# rgbstripe_fft_lochraster.net
KiCad netlist of a schematic drawn in EAGLE
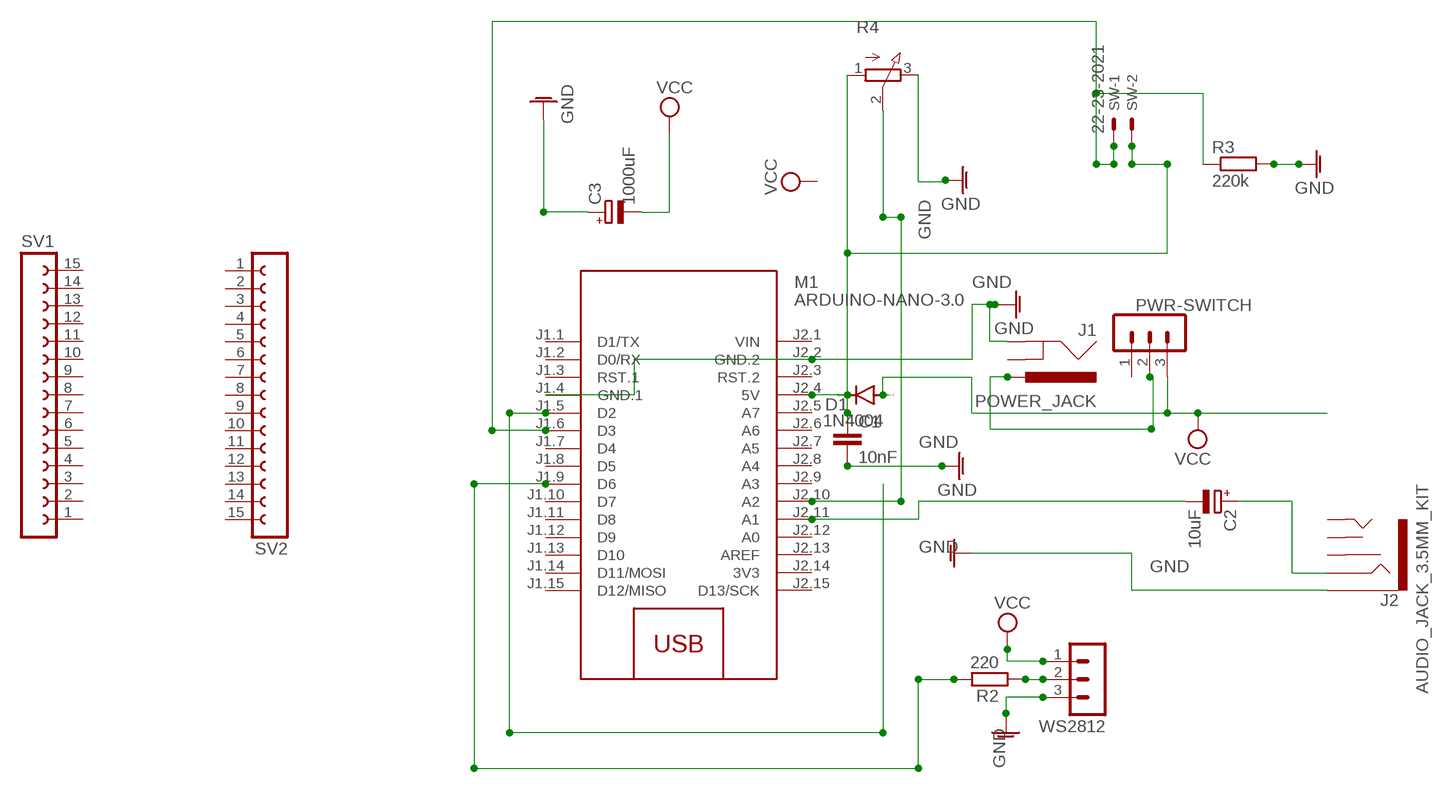
[diagram p0: schematic, sheet 1]

(export (version "E")
  (design (tool "Eeschema 10.0.6"))
  (components
    (comp (ref "C1")
      (value "10nF")
      (footprint "eagle-import:C050-024X044")
      (libsource (lib "eagle-import") (part "C-EU050-024X044"))
    )
    (comp (ref "C2")
      (value "10uF")
      (footprint "eagle-import:E2,5-6")
      (libsource (lib "eagle-import") (part "CPOL-EUE2.5-6"))
    )
    (comp (ref "C3")
      (value "1000uF")
      (footprint "eagle-import:E3,5-8")
      (libsource (lib "eagle-import") (part "CPOL-EUE3.5-8"))
    )
    (comp (ref "D1")
      (value "1N4004")
      (footprint "eagle-import:DO41-10")
      (libsource (lib "eagle-import") (part "1N4004"))
    )
    (comp (ref "J1")
      (value "POWER_JACK")
      (footprint "eagle-import:POWER_JACK_PTH")
      (libsource (lib "eagle-import") (part "POWER_JACK"))
    )
    (comp (ref "J2")
      (value "AUDIO_JACK_3.5MM_KIT")
      (footprint "eagle-import:AUDIO-JACK-KIT")
      (libsource (lib "eagle-import") (part "AUDIO_JACK_3.5MM_KIT"))
    )
    (comp (ref "M1")
      (value "ARDUINO-NANO-3.0")
      (footprint "eagle-import:ARDUINO-NANO-3.0")
      (libsource (lib "eagle-import") (part "ARDUINO-NANO-3.0"))
    )
    (comp (ref "PWR-SWITCH")
      (value "MA03-1")
      (footprint "eagle-import:MA03-1")
      (libsource (lib "eagle-import") (part "MA03-1"))
    )
    (comp (ref "R2")
      (value "220")
      (footprint "eagle-import:0204_5")
      (libsource (lib "eagle-import") (part "R-EU_0204/5"))
    )
    (comp (ref "R3")
      (value "220k")
      (footprint "eagle-import:0204_7")
      (libsource (lib "eagle-import") (part "R-EU_0204/7"))
    )
    (comp (ref "R4")
      (value "3RP/1610N")
      (footprint "eagle-import:3RP_1610N")
      (libsource (lib "eagle-import") (part "3RP/1610N"))
    )
    (comp (ref "SV1")
      (value "FE15-1")
      (footprint "eagle-import:FE15")
      (libsource (lib "eagle-import") (part "FE15-1"))
    )
    (comp (ref "SV2")
      (value "FE15-1")
      (footprint "eagle-import:FE15")
      (libsource (lib "eagle-import") (part "FE15-1"))
    )
    (comp (ref "SW")
      (value "22-23-2021")
      (footprint "eagle-import:22-23-2021")
      (fields (field (name "MF") "MOLEX"))
      (libsource (lib "eagle-import") (part "22-23-2021"))
    )
    (comp (ref "WS2812")
      (value "MA03-1")
      (footprint "eagle-import:MA03-1")
      (libsource (lib "eagle-import") (part "MA03-1"))
    )
  )
  (nets
    (net (code "1") (name "/3V3") (class "Default")
      (node (ref "M1") (pin "J2.14") (pinfunction "3V3_J2.14") (pintype "power_in"))
    )
    (net (code "2") (name "/VIN") (class "Default")
      (node (ref "M1") (pin "J2.1") (pinfunction "VIN_J2.1") (pintype "power_in"))
    )
    (net (code "3") (name "GND") (class "Default")
      (node (ref "C1") (pin "2") (pinfunction "2_2") (pintype "passive"))
      (node (ref "C3") (pin "+") (pinfunction "+_+") (pintype "passive"))
      (node (ref "J1") (pin "GND") (pinfunction "GND_GND") (pintype "bidirectional"))
      (node (ref "J2") (pin "SLEEVE") (pinfunction "SLEEVE_SLEEVE") (pintype "bidirectional"))
      (node (ref "M1") (pin "J1.4") (pinfunction "GND.1_J1.4") (pintype "power_in"))
      (node (ref "M1") (pin "J2.2") (pinfunction "GND.2_J2.2") (pintype "power_in"))
      (node (ref "R3") (pin "2") (pinfunction "2_2") (pintype "passive"))
      (node (ref "R4") (pin "3") (pinfunction "E_3") (pintype "passive"))
      (node (ref "WS2812") (pin "3") (pinfunction "3_3") (pintype "passive"))
    )
    (net (code "4") (name "Net-(C2-Pad+)") (class "Default")
      (node (ref "C2") (pin "+") (pinfunction "+_+") (pintype "passive"))
      (node (ref "J2") (pin "RING") (pinfunction "RING_RING") (pintype "bidirectional"))
    )
    (net (code "5") (name "Net-(J1-PadPWR)") (class "Default")
      (node (ref "J1") (pin "PWR") (pinfunction "PWR_PWR") (pintype "bidirectional"))
      (node (ref "PWR-SWITCH") (pin "2") (pinfunction "2_2") (pintype "passive"))
    )
    (net (code "6") (name "Net-(M1-5V)") (class "Default")
      (node (ref "C1") (pin "1") (pinfunction "1_1") (pintype "passive"))
      (node (ref "D1") (pin "C") (pinfunction "C_C") (pintype "passive"))
      (node (ref "M1") (pin "J2.4") (pinfunction "5V_J2.4") (pintype "power_in"))
      (node (ref "R4") (pin "1") (pinfunction "A_1") (pintype "passive"))
      (node (ref "SW") (pin "2") (pinfunction "S_2") (pintype "passive"))
    )
    (net (code "7") (name "Net-(M1-A1)") (class "Default")
      (node (ref "C2") (pin "-") (pinfunction "-_-") (pintype "passive"))
      (node (ref "M1") (pin "J2.11") (pinfunction "A1_J2.11") (pintype "bidirectional"))
    )
    (net (code "8") (name "Net-(M1-A2)") (class "Default")
      (node (ref "M1") (pin "J2.10") (pinfunction "A2_J2.10") (pintype "bidirectional"))
      (node (ref "R4") (pin "2") (pinfunction "S_2") (pintype "passive"))
    )
    (net (code "9") (name "Net-(M1-D3)") (class "Default")
      (node (ref "M1") (pin "J1.6") (pinfunction "D3_J1.6") (pintype "bidirectional"))
      (node (ref "R3") (pin "1") (pinfunction "1_1") (pintype "passive"))
      (node (ref "SW") (pin "1") (pinfunction "S_1") (pintype "passive"))
    )
    (net (code "10") (name "Net-(M1-D6)") (class "Default")
      (node (ref "M1") (pin "J1.9") (pinfunction "D6_J1.9") (pintype "bidirectional"))
      (node (ref "R2") (pin "2") (pinfunction "2_2") (pintype "passive"))
    )
    (net (code "11") (name "Net-(R2-Pad1)") (class "Default")
      (node (ref "R2") (pin "1") (pinfunction "1_1") (pintype "passive"))
      (node (ref "WS2812") (pin "2") (pinfunction "2_2") (pintype "passive"))
    )
    (net (code "12") (name "VCC") (class "Default")
      (node (ref "C3") (pin "-") (pinfunction "-_-") (pintype "passive"))
      (node (ref "D1") (pin "A") (pinfunction "A_A") (pintype "passive"))
      (node (ref "PWR-SWITCH") (pin "3") (pinfunction "3_3") (pintype "passive"))
      (node (ref "WS2812") (pin "1") (pinfunction "1_1") (pintype "passive"))
    )
    (net (code "13") (name "unconnected-(J1-PadGNDBREAK)") (class "Default")
      (node (ref "J1") (pin "GNDBREAK") (pinfunction "GNDBREAK_GNDBREAK") (pintype "bidirectional"))
    )
    (net (code "14") (name "unconnected-(J2-PadRSH)") (class "Default")
      (node (ref "J2") (pin "RSH") (pinfunction "RSH_RSH") (pintype "bidirectional"))
    )
    (net (code "15") (name "unconnected-(J2-PadTIP)") (class "Default")
      (node (ref "J2") (pin "TIP") (pinfunction "TIP_TIP") (pintype "bidirectional"))
    )
    (net (code "16") (name "unconnected-(J2-PadTSH)") (class "Default")
      (node (ref "J2") (pin "TSH") (pinfunction "TSH_TSH") (pintype "bidirectional"))
    )
    (net (code "17") (name "unconnected-(M1-A0-PadJ2.12)") (class "Default")
      (node (ref "M1") (pin "J2.12") (pinfunction "A0_J2.12") (pintype "bidirectional"))
    )
    (net (code "18") (name "unconnected-(M1-A3-PadJ2.9)") (class "Default")
      (node (ref "M1") (pin "J2.9") (pinfunction "A3_J2.9") (pintype "bidirectional"))
    )
    (net (code "19") (name "unconnected-(M1-A4-PadJ2.8)") (class "Default")
      (node (ref "M1") (pin "J2.8") (pinfunction "A4_J2.8") (pintype "bidirectional"))
    )
    (net (code "20") (name "unconnected-(M1-A5-PadJ2.7)") (class "Default")
      (node (ref "M1") (pin "J2.7") (pinfunction "A5_J2.7") (pintype "bidirectional"))
    )
    (net (code "21") (name "unconnected-(M1-A6-PadJ2.6)") (class "Default")
      (node (ref "M1") (pin "J2.6") (pinfunction "A6_J2.6") (pintype "bidirectional"))
    )
    (net (code "22") (name "unconnected-(M1-A7-PadJ2.5)") (class "Default")
      (node (ref "M1") (pin "J2.5") (pinfunction "A7_J2.5") (pintype "bidirectional"))
    )
    (net (code "23") (name "unconnected-(M1-AREF-PadJ2.13)") (class "Default")
      (node (ref "M1") (pin "J2.13") (pinfunction "AREF_J2.13") (pintype "bidirectional"))
    )
    (net (code "24") (name "unconnected-(M1-D0{slash}RX-PadJ1.2)") (class "Default")
      (node (ref "M1") (pin "J1.2") (pinfunction "D0/RX_J1.2") (pintype "bidirectional"))
    )
    (net (code "25") (name "unconnected-(M1-D1{slash}TX-PadJ1.1)") (class "Default")
      (node (ref "M1") (pin "J1.1") (pinfunction "D1/TX_J1.1") (pintype "bidirectional"))
    )
    (net (code "26") (name "unconnected-(M1-D2-PadJ1.5)") (class "Default")
      (node (ref "M1") (pin "J1.5") (pinfunction "D2_J1.5") (pintype "bidirectional"))
    )
    (net (code "27") (name "unconnected-(M1-D4-PadJ1.7)") (class "Default")
      (node (ref "M1") (pin "J1.7") (pinfunction "D4_J1.7") (pintype "bidirectional"))
    )
    (net (code "28") (name "unconnected-(M1-D5-PadJ1.8)") (class "Default")
      (node (ref "M1") (pin "J1.8") (pinfunction "D5_J1.8") (pintype "bidirectional"))
    )
    (net (code "29") (name "unconnected-(M1-D7-PadJ1.10)") (class "Default")
      (node (ref "M1") (pin "J1.10") (pinfunction "D7_J1.10") (pintype "bidirectional"))
    )
    (net (code "30") (name "unconnected-(M1-D8-PadJ1.11)") (class "Default")
      (node (ref "M1") (pin "J1.11") (pinfunction "D8_J1.11") (pintype "bidirectional"))
    )
    (net (code "31") (name "unconnected-(M1-D9-PadJ1.12)") (class "Default")
      (node (ref "M1") (pin "J1.12") (pinfunction "D9_J1.12") (pintype "bidirectional"))
    )
    (net (code "32") (name "unconnected-(M1-D10-PadJ1.13)") (class "Default")
      (node (ref "M1") (pin "J1.13") (pinfunction "D10_J1.13") (pintype "bidirectional"))
    )
    (net (code "33") (name "unconnected-(M1-D11{slash}MOSI-PadJ1.14)") (class "Default")
      (node (ref "M1") (pin "J1.14") (pinfunction "D11/MOSI_J1.14") (pintype "bidirectional"))
    )
    (net (code "34") (name "unconnected-(M1-D12{slash}MISO-PadJ1.15)") (class "Default")
      (node (ref "M1") (pin "J1.15") (pinfunction "D12/MISO_J1.15") (pintype "bidirectional"))
    )
    (net (code "35") (name "unconnected-(M1-D13{slash}SCK-PadJ2.15)") (class "Default")
      (node (ref "M1") (pin "J2.15") (pinfunction "D13/SCK_J2.15") (pintype "bidirectional"))
    )
    (net (code "36") (name "unconnected-(M1-RST.1-PadJ1.3)") (class "Default")
      (node (ref "M1") (pin "J1.3") (pinfunction "RST.1_J1.3") (pintype "bidirectional"))
    )
    (net (code "37") (name "unconnected-(M1-RST.2-PadJ2.3)") (class "Default")
      (node (ref "M1") (pin "J2.3") (pinfunction "RST.2_J2.3") (pintype "bidirectional"))
    )
    (net (code "38") (name "unconnected-(PWR-SWITCH-Pad1)") (class "Default")
      (node (ref "PWR-SWITCH") (pin "1") (pinfunction "1_1") (pintype "passive"))
    )
    (net (code "39") (name "unconnected-(SV1-Pad1)") (class "Default")
      (node (ref "SV1") (pin "1") (pinfunction "1_1") (pintype "passive"))
    )
    (net (code "40") (name "unconnected-(SV1-Pad2)") (class "Default")
      (node (ref "SV1") (pin "2") (pinfunction "2_2") (pintype "passive"))
    )
    (net (code "41") (name "unconnected-(SV1-Pad3)") (class "Default")
      (node (ref "SV1") (pin "3") (pinfunction "3_3") (pintype "passive"))
    )
    (net (code "42") (name "unconnected-(SV1-Pad4)") (class "Default")
      (node (ref "SV1") (pin "4") (pinfunction "4_4") (pintype "passive"))
    )
    (net (code "43") (name "unconnected-(SV1-Pad5)") (class "Default")
      (node (ref "SV1") (pin "5") (pinfunction "5_5") (pintype "passive"))
    )
    (net (code "44") (name "unconnected-(SV1-Pad6)") (class "Default")
      (node (ref "SV1") (pin "6") (pinfunction "6_6") (pintype "passive"))
    )
    (net (code "45") (name "unconnected-(SV1-Pad7)") (class "Default")
      (node (ref "SV1") (pin "7") (pinfunction "7_7") (pintype "passive"))
    )
    (net (code "46") (name "unconnected-(SV1-Pad8)") (class "Default")
      (node (ref "SV1") (pin "8") (pinfunction "8_8") (pintype "passive"))
    )
    (net (code "47") (name "unconnected-(SV1-Pad9)") (class "Default")
      (node (ref "SV1") (pin "9") (pinfunction "9_9") (pintype "passive"))
    )
    (net (code "48") (name "unconnected-(SV1-Pad10)") (class "Default")
      (node (ref "SV1") (pin "10") (pinfunction "10_10") (pintype "passive"))
    )
    (net (code "49") (name "unconnected-(SV1-Pad11)") (class "Default")
      (node (ref "SV1") (pin "11") (pinfunction "11_11") (pintype "passive"))
    )
    (net (code "50") (name "unconnected-(SV1-Pad12)") (class "Default")
      (node (ref "SV1") (pin "12") (pinfunction "12_12") (pintype "passive"))
    )
    (net (code "51") (name "unconnected-(SV1-Pad13)") (class "Default")
      (node (ref "SV1") (pin "13") (pinfunction "13_13") (pintype "passive"))
    )
    (net (code "52") (name "unconnected-(SV1-Pad14)") (class "Default")
      (node (ref "SV1") (pin "14") (pinfunction "14_14") (pintype "passive"))
    )
    (net (code "53") (name "unconnected-(SV1-Pad15)") (class "Default")
      (node (ref "SV1") (pin "15") (pinfunction "15_15") (pintype "passive"))
    )
    (net (code "54") (name "unconnected-(SV2-Pad1)") (class "Default")
      (node (ref "SV2") (pin "1") (pinfunction "1_1") (pintype "passive"))
    )
    (net (code "55") (name "unconnected-(SV2-Pad2)") (class "Default")
      (node (ref "SV2") (pin "2") (pinfunction "2_2") (pintype "passive"))
    )
    (net (code "56") (name "unconnected-(SV2-Pad3)") (class "Default")
      (node (ref "SV2") (pin "3") (pinfunction "3_3") (pintype "passive"))
    )
    (net (code "57") (name "unconnected-(SV2-Pad4)") (class "Default")
      (node (ref "SV2") (pin "4") (pinfunction "4_4") (pintype "passive"))
    )
    (net (code "58") (name "unconnected-(SV2-Pad5)") (class "Default")
      (node (ref "SV2") (pin "5") (pinfunction "5_5") (pintype "passive"))
    )
    (net (code "59") (name "unconnected-(SV2-Pad6)") (class "Default")
      (node (ref "SV2") (pin "6") (pinfunction "6_6") (pintype "passive"))
    )
    (net (code "60") (name "unconnected-(SV2-Pad7)") (class "Default")
      (node (ref "SV2") (pin "7") (pinfunction "7_7") (pintype "passive"))
    )
    (net (code "61") (name "unconnected-(SV2-Pad8)") (class "Default")
      (node (ref "SV2") (pin "8") (pinfunction "8_8") (pintype "passive"))
    )
    (net (code "62") (name "unconnected-(SV2-Pad9)") (class "Default")
      (node (ref "SV2") (pin "9") (pinfunction "9_9") (pintype "passive"))
    )
    (net (code "63") (name "unconnected-(SV2-Pad10)") (class "Default")
      (node (ref "SV2") (pin "10") (pinfunction "10_10") (pintype "passive"))
    )
    (net (code "64") (name "unconnected-(SV2-Pad11)") (class "Default")
      (node (ref "SV2") (pin "11") (pinfunction "11_11") (pintype "passive"))
    )
    (net (code "65") (name "unconnected-(SV2-Pad12)") (class "Default")
      (node (ref "SV2") (pin "12") (pinfunction "12_12") (pintype "passive"))
    )
    (net (code "66") (name "unconnected-(SV2-Pad13)") (class "Default")
      (node (ref "SV2") (pin "13") (pinfunction "13_13") (pintype "passive"))
    )
    (net (code "67") (name "unconnected-(SV2-Pad14)") (class "Default")
      (node (ref "SV2") (pin "14") (pinfunction "14_14") (pintype "passive"))
    )
    (net (code "68") (name "unconnected-(SV2-Pad15)") (class "Default")
      (node (ref "SV2") (pin "15") (pinfunction "15_15") (pintype "passive"))
    )
  )
)
